# voltage_measurement.net
KiCad netlist of a schematic drawn in Altium Designer
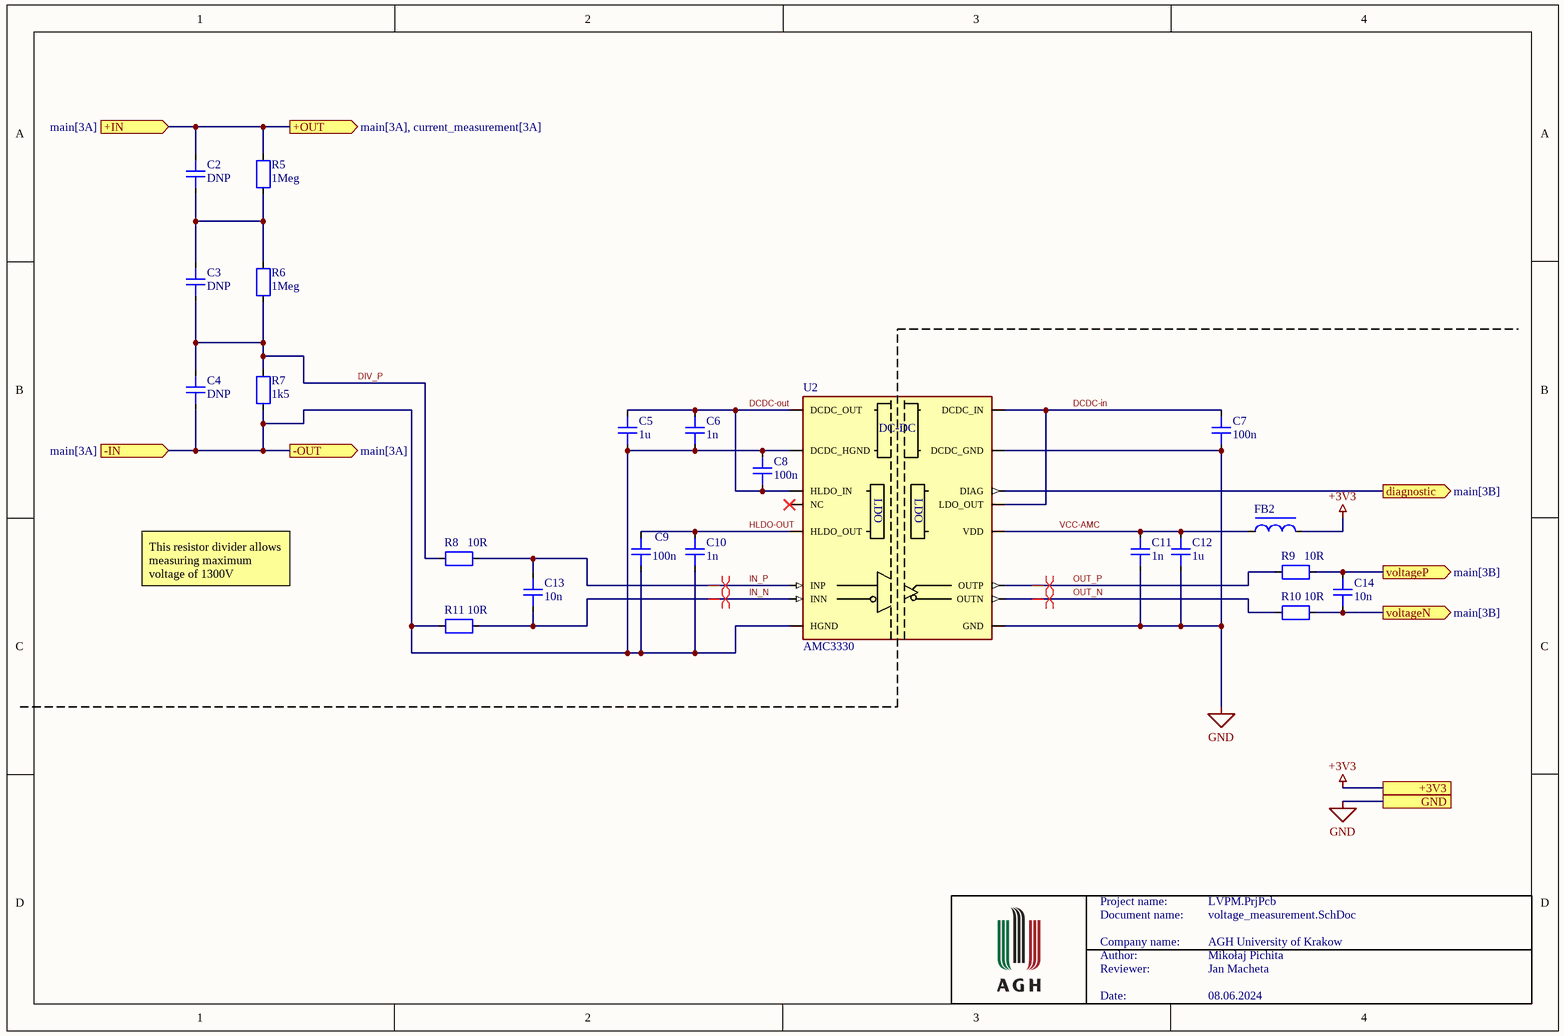
[diagram p0: voltage_measurement.SchDoc]

(export (version "E")
  (design (tool "Eeschema 10.0.6"))
  (components
    (comp (ref "C2")
      (value "DNP")
      (footprint "CAP1206")
      (libsource (lib "Integrated_Library_main") (part "Capacitor"))
    )
    (comp (ref "C3")
      (value "DNP")
      (footprint "CAP1206")
      (libsource (lib "Integrated_Library_main") (part "Capacitor"))
    )
    (comp (ref "C4")
      (value "DNP")
      (footprint "CAP1206")
      (libsource (lib "Integrated_Library_main") (part "Capacitor"))
    )
    (comp (ref "C5")
      (value "1u")
      (footprint "CAP0603")
      (libsource (lib "schematic_library") (part "Capacitor"))
    )
    (comp (ref "C6")
      (value "1n")
      (footprint "CAP0603")
      (libsource (lib "schematic_library") (part "Capacitor"))
    )
    (comp (ref "C7")
      (value "100n")
      (footprint "CAP0603")
      (libsource (lib "schematic_library") (part "Capacitor"))
    )
    (comp (ref "C8")
      (value "100n")
      (footprint "CAP0603")
      (libsource (lib "schematic_library") (part "Capacitor"))
    )
    (comp (ref "C9")
      (value "100n")
      (footprint "CAP1206")
      (libsource (lib "schematic_library") (part "Capacitor"))
    )
    (comp (ref "C10")
      (value "1n")
      (footprint "CAP1206")
      (libsource (lib "schematic_library") (part "Capacitor"))
    )
    (comp (ref "C11")
      (value "1n")
      (footprint "CAP1206")
      (libsource (lib "schematic_library") (part "Capacitor"))
    )
    (comp (ref "C12")
      (value "1u")
      (footprint "CAP1206")
      (libsource (lib "schematic_library") (part "Capacitor"))
    )
    (comp (ref "C13")
      (value "10n")
      (footprint "CAP0603")
      (libsource (lib "Integrated_Library_main") (part "Capacitor"))
    )
    (comp (ref "C14")
      (value "10n")
      (footprint "CAP0603")
      (libsource (lib "schematic_library") (part "Capacitor"))
    )
    (comp (ref "FB2")
      (value "*")
      (footprint "FB0402")
      (libsource (lib "Integrated_Library_main") (part "Ferrite Bead"))
    )
    (comp (ref "R5")
      (value "1Meg")
      (footprint "RESC3215X06N")
      (libsource (lib "Integrated_Library_main") (part "Resistor"))
    )
    (comp (ref "R6")
      (value "1Meg")
      (footprint "RESC3215X06N")
      (libsource (lib "Integrated_Library_main") (part "Resistor"))
    )
    (comp (ref "R7")
      (value "1k5")
      (footprint "RESC3215X06N")
      (libsource (lib "Integrated_Library_main") (part "Resistor"))
    )
    (comp (ref "R8")
      (value "10R")
      (footprint "RES0603")
      (libsource (lib "Integrated_Library_main") (part "Resistor"))
    )
    (comp (ref "R9")
      (value "10R")
      (footprint "RES0603")
      (libsource (lib "schematic_library") (part "Resistor"))
    )
    (comp (ref "R10")
      (value "10R")
      (footprint "RES0603")
      (libsource (lib "schematic_library") (part "Resistor"))
    )
    (comp (ref "R11")
      (value "10R")
      (footprint "RES0603")
      (libsource (lib "Integrated_Library_main") (part "Resistor"))
    )
    (comp (ref "U2")
      (value "AMC3330")
      (footprint "SOIC127P1030X265-16N")
      (description "±1-V input, precision voltage sensing reinforced isolated amplifier with integrated DC/DC")
      (libsource (lib "Integrated_Library_main") (part "AMC3330"))
    )
  )
  (nets
    (net (code "1") (name "+3V3") (class "Default") (node (ref "FB2") (pin "2") (pintype "passive")))
    (net (code "2") (name "/+IN") (class "Default")
      (node (ref "C2") (pin "1") (pintype "passive"))
      (node (ref "R5") (pin "1") (pintype "passive"))
    )
    (net (code "3") (name "/-IN") (class "Default")
      (node (ref "C10") (pin "2") (pintype "passive"))
      (node (ref "C4") (pin "2") (pintype "passive"))
      (node (ref "C5") (pin "2") (pintype "passive"))
      (node (ref "C6") (pin "2") (pintype "passive"))
      (node (ref "C8") (pin "1") (pintype "passive"))
      (node (ref "C9") (pin "2") (pintype "passive"))
      (node (ref "R11") (pin "1") (pintype "passive"))
      (node (ref "R7") (pin "2") (pintype "passive"))
      (node (ref "U2") (pin "2") (pinfunction "DCDC_HGND_2") (pintype "passive"))
      (node (ref "U2") (pin "8") (pinfunction "HGND_8") (pintype "passive"))
    )
    (net (code "4") (name "/DCDC-in") (class "Default")
      (node (ref "C7") (pin "1") (pintype "passive"))
      (node (ref "U2") (pin "13") (pinfunction "LDO_OUT_13") (pintype "power_in"))
      (node (ref "U2") (pin "16") (pinfunction "DCDC_IN_16") (pintype "power_in"))
    )
    (net (code "5") (name "/DCDC-out") (class "Default")
      (node (ref "C5") (pin "1") (pintype "passive"))
      (node (ref "C6") (pin "1") (pintype "passive"))
      (node (ref "C8") (pin "2") (pintype "passive"))
      (node (ref "U2") (pin "1") (pinfunction "DCDC_OUT_1") (pintype "power_in"))
      (node (ref "U2") (pin "3") (pinfunction "HLDO_IN_3") (pintype "power_in"))
    )
    (net (code "6") (name "/DIV_P") (class "Default")
      (node (ref "C3") (pin "2") (pintype "passive"))
      (node (ref "C4") (pin "1") (pintype "passive"))
      (node (ref "R6") (pin "2") (pintype "passive"))
      (node (ref "R7") (pin "1") (pintype "passive"))
      (node (ref "R8") (pin "1") (pintype "passive"))
    )
    (net (code "7") (name "/HLDO-OUT") (class "Default")
      (node (ref "C10") (pin "1") (pintype "passive"))
      (node (ref "C9") (pin "1") (pintype "passive"))
      (node (ref "U2") (pin "5") (pinfunction "HLDO_OUT_5") (pintype "power_in"))
    )
    (net (code "8") (name "/IN_N") (class "Default")
      (node (ref "C13") (pin "2") (pintype "passive"))
      (node (ref "R11") (pin "2") (pintype "passive"))
      (node (ref "U2") (pin "7") (pinfunction "INN_7") (pintype "input"))
    )
    (net (code "9") (name "/IN_P") (class "Default")
      (node (ref "C13") (pin "1") (pintype "passive"))
      (node (ref "R8") (pin "2") (pintype "passive"))
      (node (ref "U2") (pin "6") (pinfunction "INP_6") (pintype "input"))
    )
    (net (code "10") (name "/OUT_N") (class "Default")
      (node (ref "R10") (pin "2") (pintype "passive"))
      (node (ref "U2") (pin "10") (pinfunction "OUTN_10") (pintype "output"))
    )
    (net (code "11") (name "/OUT_P") (class "Default")
      (node (ref "R9") (pin "2") (pintype "passive"))
      (node (ref "U2") (pin "11") (pinfunction "OUTP_11") (pintype "output"))
    )
    (net (code "12") (name "/VCC-AMC") (class "Default")
      (node (ref "C11") (pin "1") (pintype "passive"))
      (node (ref "C12") (pin "1") (pintype "passive"))
      (node (ref "FB2") (pin "1") (pintype "passive"))
      (node (ref "U2") (pin "12") (pinfunction "VDD_12") (pintype "power_in"))
    )
    (net (code "13") (name "/diagnostic") (class "Default")
      (node (ref "U2") (pin "14") (pinfunction "DIAG_14") (pintype "output"))
    )
    (net (code "14") (name "/voltageN") (class "Default")
      (node (ref "C14") (pin "1") (pintype "passive"))
      (node (ref "R10") (pin "1") (pintype "passive"))
    )
    (net (code "15") (name "/voltageP") (class "Default")
      (node (ref "C14") (pin "2") (pintype "passive"))
      (node (ref "R9") (pin "1") (pintype "passive"))
    )
    (net (code "16") (name "GND") (class "Default")
      (node (ref "C11") (pin "2") (pintype "passive"))
      (node (ref "C12") (pin "2") (pintype "passive"))
      (node (ref "C7") (pin "2") (pintype "passive"))
      (node (ref "U2") (pin "15") (pinfunction "DCDC_GND_15") (pintype "power_in"))
      (node (ref "U2") (pin "9") (pinfunction "GND_9") (pintype "power_in"))
    )
    (net (code "17") (name "Net-(C2-Pad2)") (class "Default")
      (node (ref "C2") (pin "2") (pintype "passive"))
      (node (ref "C3") (pin "1") (pintype "passive"))
      (node (ref "R5") (pin "2") (pintype "passive"))
      (node (ref "R6") (pin "1") (pintype "passive"))
    )
    (net (code "18") (name "unconnected-(U2-NC-Pad4)") (class "Default")
      (node (ref "U2") (pin "4") (pinfunction "NC_4") (pintype "passive+no_connect"))
    )
  )
)
